# power.net
KiCad netlist of a schematic drawn in Altium Designer
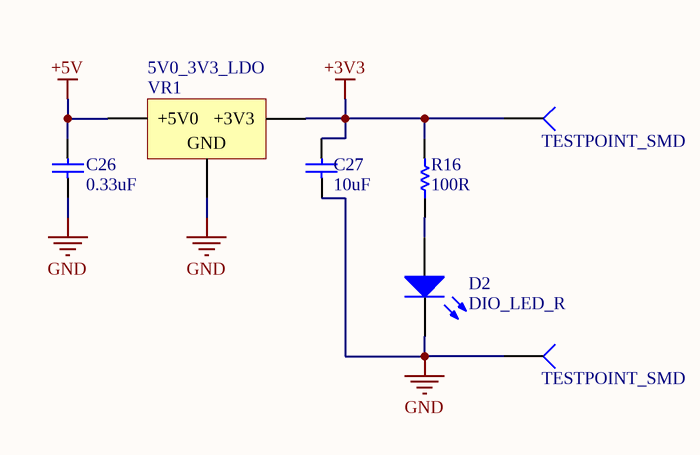
[diagram p0: power.SchDoc]

(export (version "E")
  (design (tool "Eeschema 10.0.6"))
  (components
    (comp (ref "3V3")
      (value "TESTPOINT_SMD")
      (footprint "TESTPOINT")
      (libsource (lib "UWRT_Schematic_Library_2019") (part "TESTPOINT_SMD"))
    )
    (comp (ref "C26")
      (value "0.33uF")
      (footprint "CAPC0603(1608)55_N")
      (description "CAP CER 0.33UF 16V X7R 0603")
      (fields
        (field (name "MANUFACTURER") "Murata Electronics North America")
        (field (name "MPN") "GCM188R71C334KA37D")
      )
      (libsource (lib "UWRT_Schematic_Library_2019") (part "CAP_0.33uF_16V_0603"))
    )
    (comp (ref "C27")
      (value "10uF")
      (footprint "AVX-CAPC3528_V")
      (description "CAP CER 10UF 10V X5R 0603")
      (fields (field (name "MANUFACTURER") "Yageo") (field (name "MPN") "CC0603MRX5R6BB106"))
      (libsource (lib "UWRT_Schematic_Library_2019") (part "CAP_10uF_0603"))
    )
    (comp (ref "D2")
      (value "DIO_LED_R")
      (footprint "LED_0805_LINE")
      (description "LED RED DIFFUSED 0805 SMD")
      (fields (field (name "MANUFACTURER") "OSRAM") (field (name "MPN") "LS R976-NR-1"))
      (libsource (lib "UWRT_Schematic_Library_2019") (part "DIO_LED_R"))
    )
    (comp (ref "GND")
      (value "TESTPOINT_SMD")
      (footprint "TESTPOINT")
      (libsource (lib "UWRT_Schematic_Library_2019") (part "TESTPOINT_SMD"))
    )
    (comp (ref "R16")
      (value "100R")
      (footprint "RESC0603(1608)_N")
      (description "RES SMD 100 OHM 1% 1/10W 0603")
      (fields (field (name "MANUFACTURER") "Yageo") (field (name "TOLERANCE") "1%"))
      (libsource (lib "UWRT_Schematic_Library_2019") (part "RES_100R_0603"))
    )
    (comp (ref "VR1")
      (value "5V0_3V3_LDO")
      (footprint "UWRT_Footprint_Library_2019:VOLTAGE_REGULATOR")
      (description "IC REG LINEAR 3.3V 1A DPAK")
      (fields (field (name "MANUFACTURER") "ON Semiconductor") (field (name "MPN") "NCP1117DT33T5G"))
      (libsource (lib "UWRT_Schematic_Library_2019") (part "5V0_3V3_LDO"))
    )
  )
  (nets
    (net (code "1") (name "+3V3") (class "Default")
      (node (ref "3V3") (pin "1") (pinfunction "=value_1") (pintype "passive"))
      (node (ref "C27") (pin "2") (pinfunction "2_2") (pintype "passive"))
      (node (ref "R16") (pin "2") (pinfunction "2_2") (pintype "passive"))
      (node (ref "VR1") (pin "2") (pinfunction "+3V3_2") (pintype "passive"))
    )
    (net (code "2") (name "+5V") (class "Default")
      (node (ref "C26") (pin "2") (pinfunction "2_2") (pintype "passive"))
      (node (ref "VR1") (pin "3") (pinfunction "+5V0_3") (pintype "passive"))
    )
    (net (code "3") (name "GND") (class "Default")
      (node (ref "C26") (pin "1") (pinfunction "1_1") (pintype "passive"))
      (node (ref "C27") (pin "1") (pinfunction "1_1") (pintype "passive"))
      (node (ref "D2") (pin "2") (pinfunction "K_2") (pintype "passive"))
      (node (ref "GND") (pin "1") (pinfunction "=value_1") (pintype "passive"))
      (node (ref "VR1") (pin "1") (pinfunction "GND_1") (pintype "passive"))
    )
    (net (code "4") (name "Net-(D2-A)") (class "Default")
      (node (ref "D2") (pin "1") (pinfunction "A_1") (pintype "passive"))
      (node (ref "R16") (pin "1") (pinfunction "1_1") (pintype "passive"))
    )
  )
)
